# QuadCopterV2.net
KiCad netlist of a schematic drawn in EAGLE
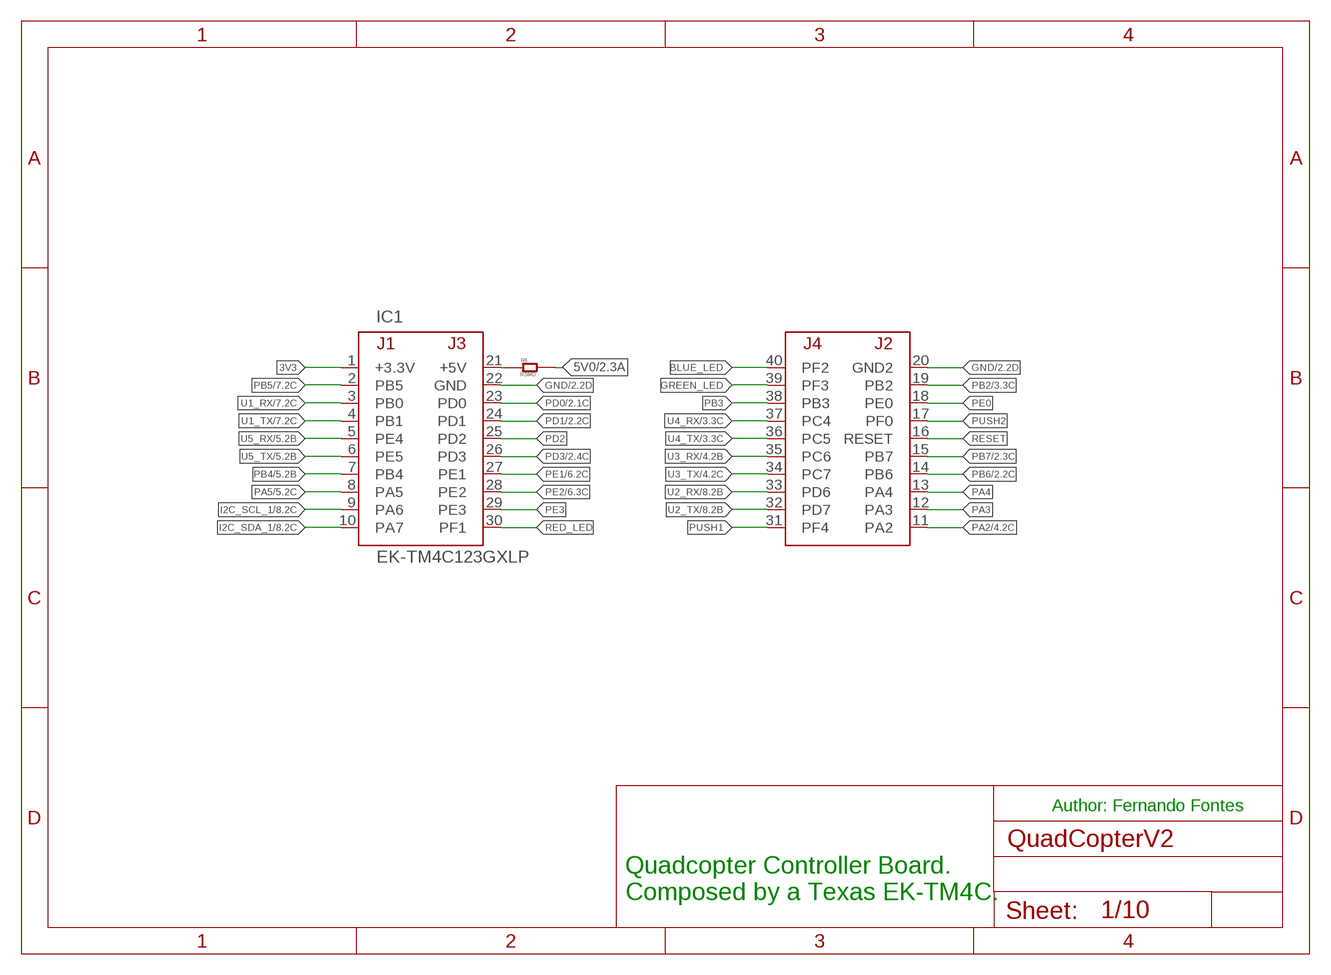
[diagram p0: schematic, sheet 1]
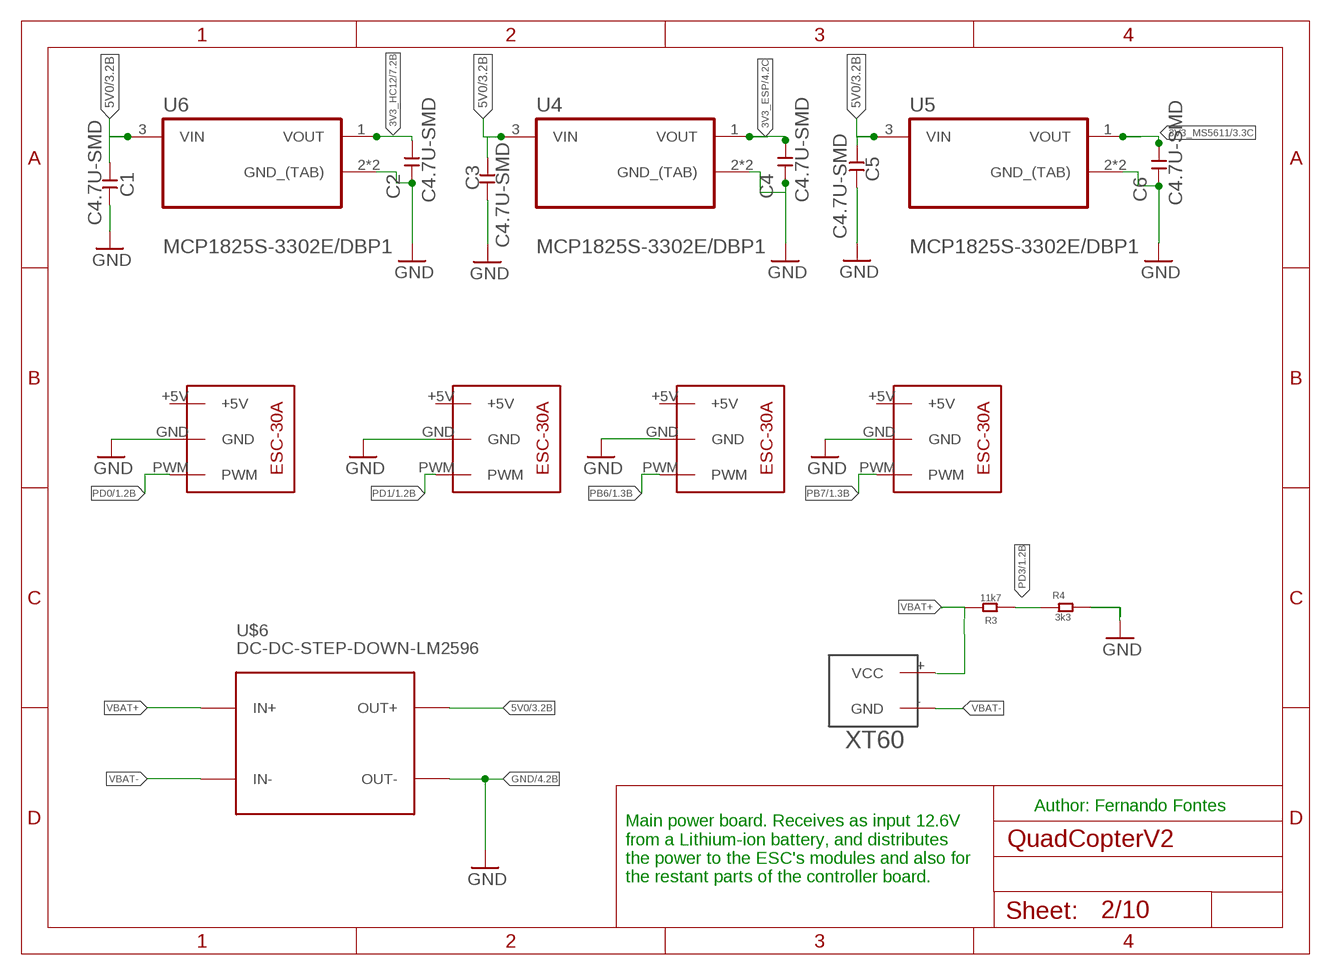
[diagram p1: schematic, sheet 2]
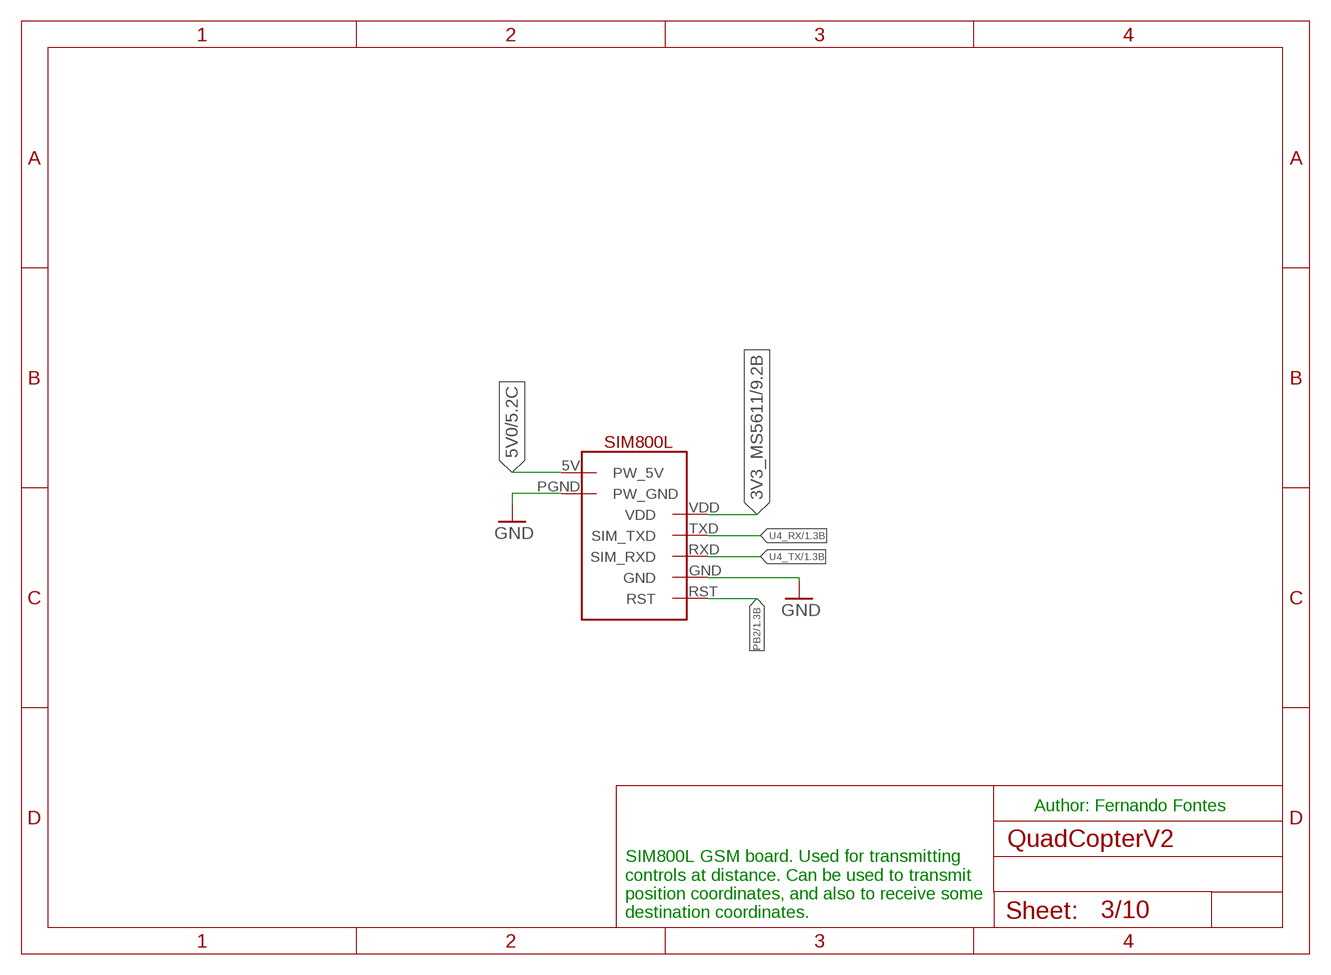
[diagram p2: schematic, sheet 3]
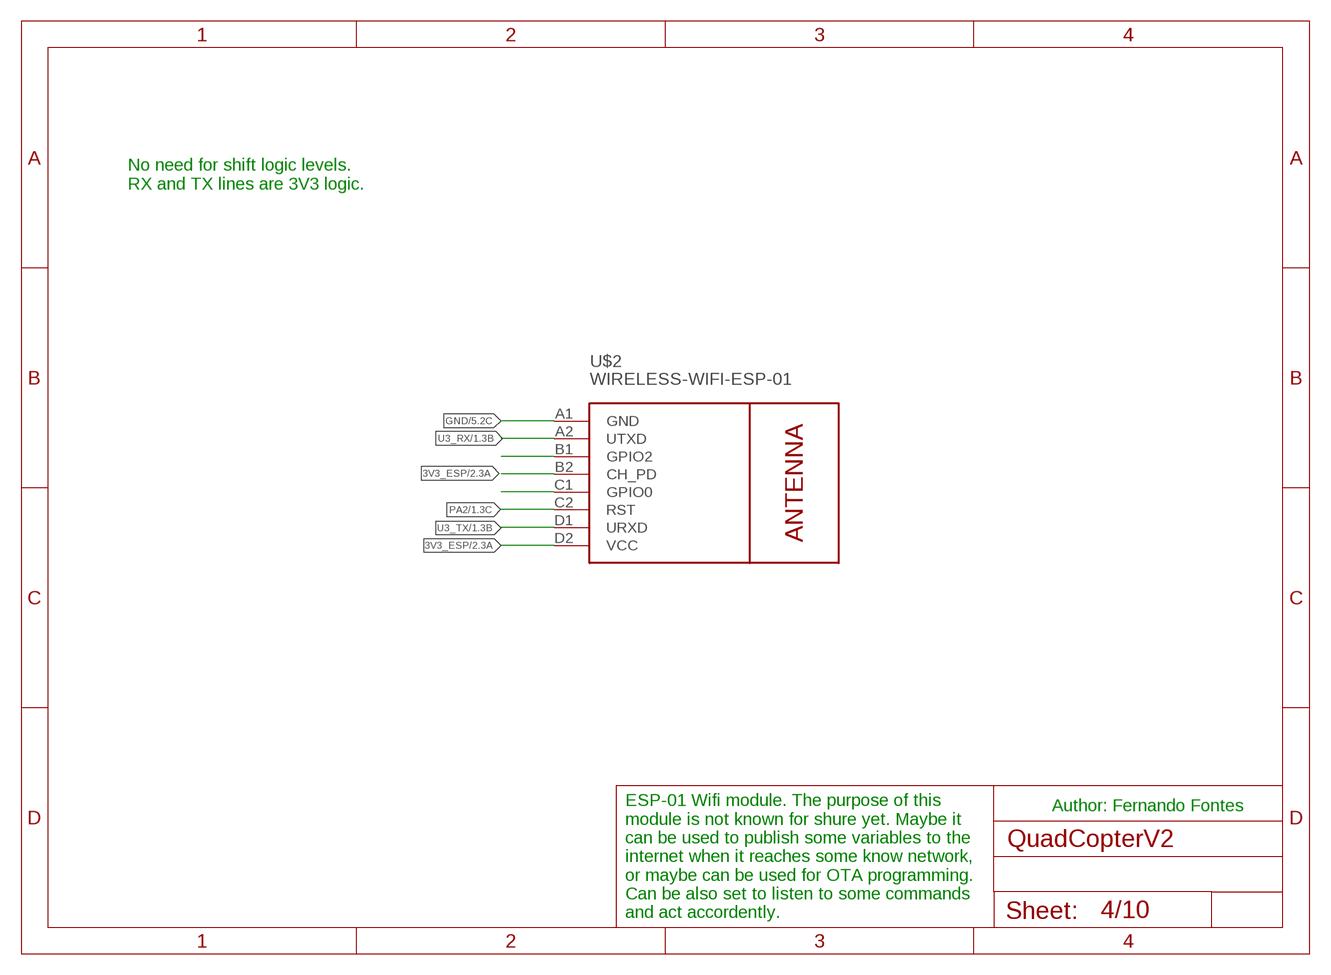
[diagram p3: schematic, sheet 4]
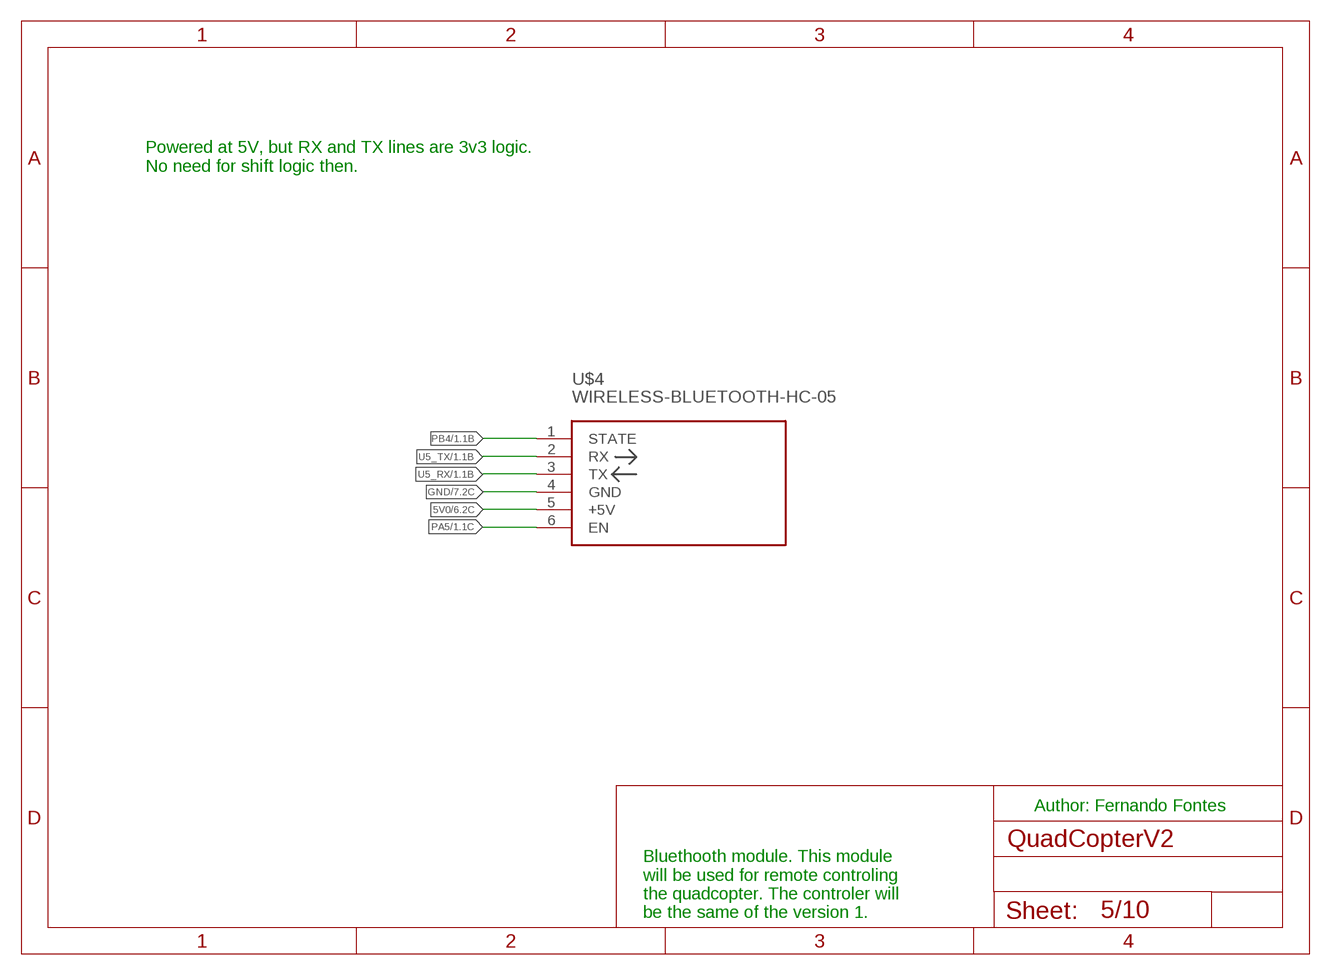
[diagram p4: schematic, sheet 5]
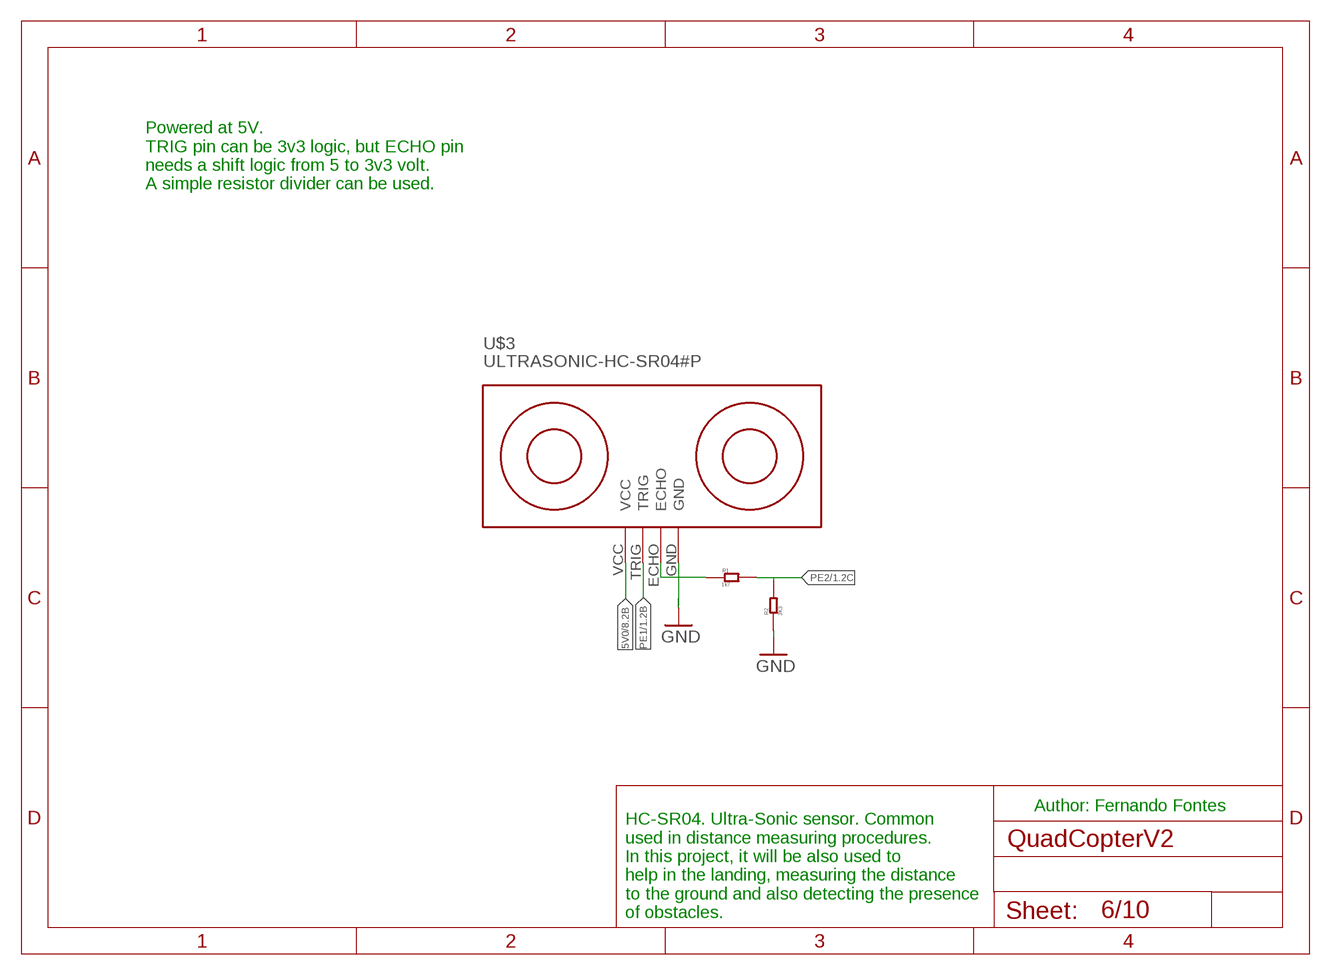
[diagram p5: schematic, sheet 6]
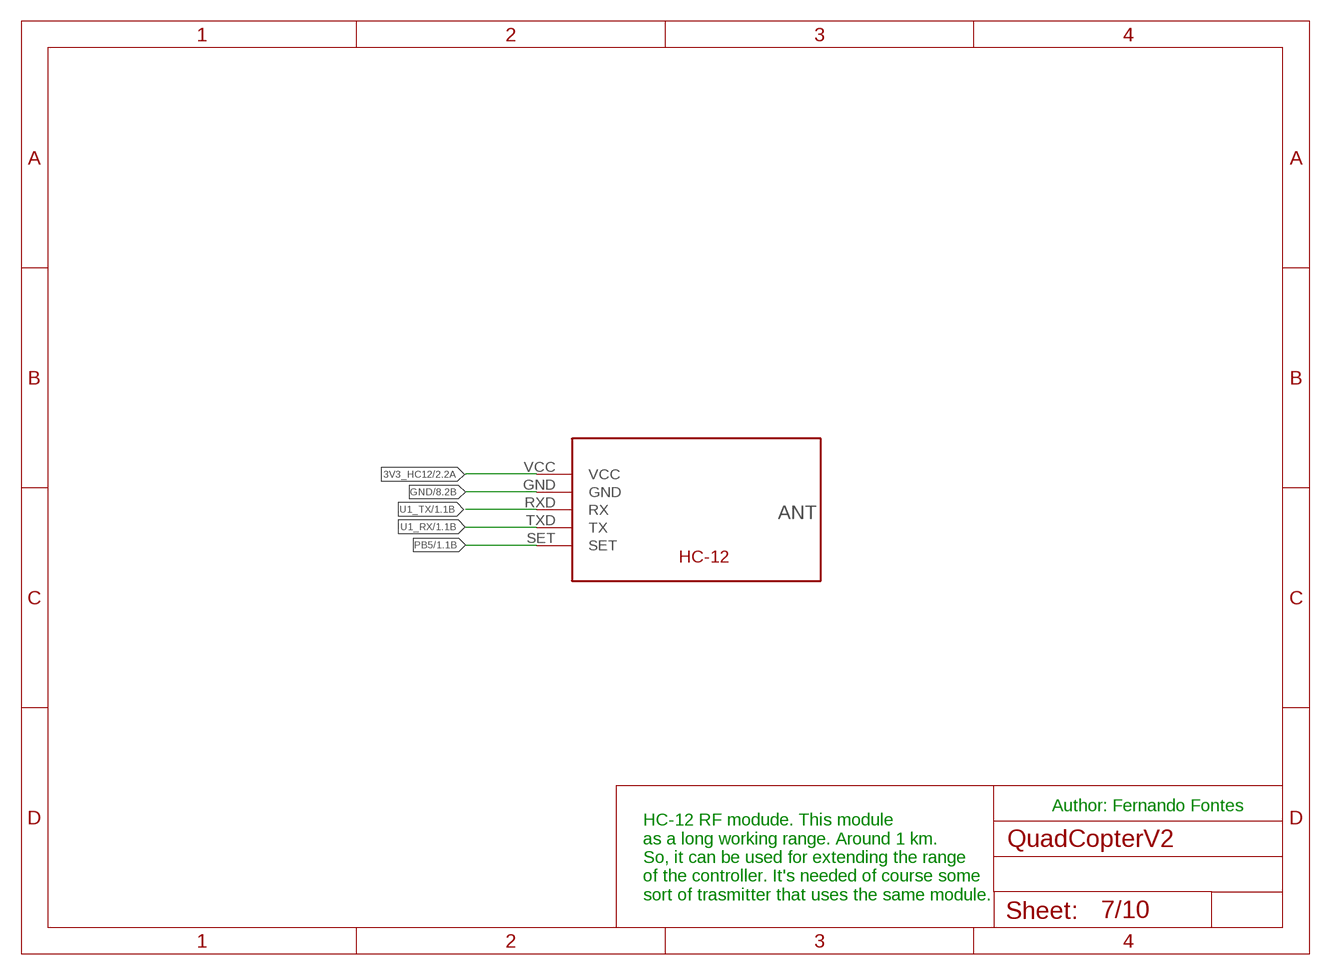
[diagram p6: schematic, sheet 7]
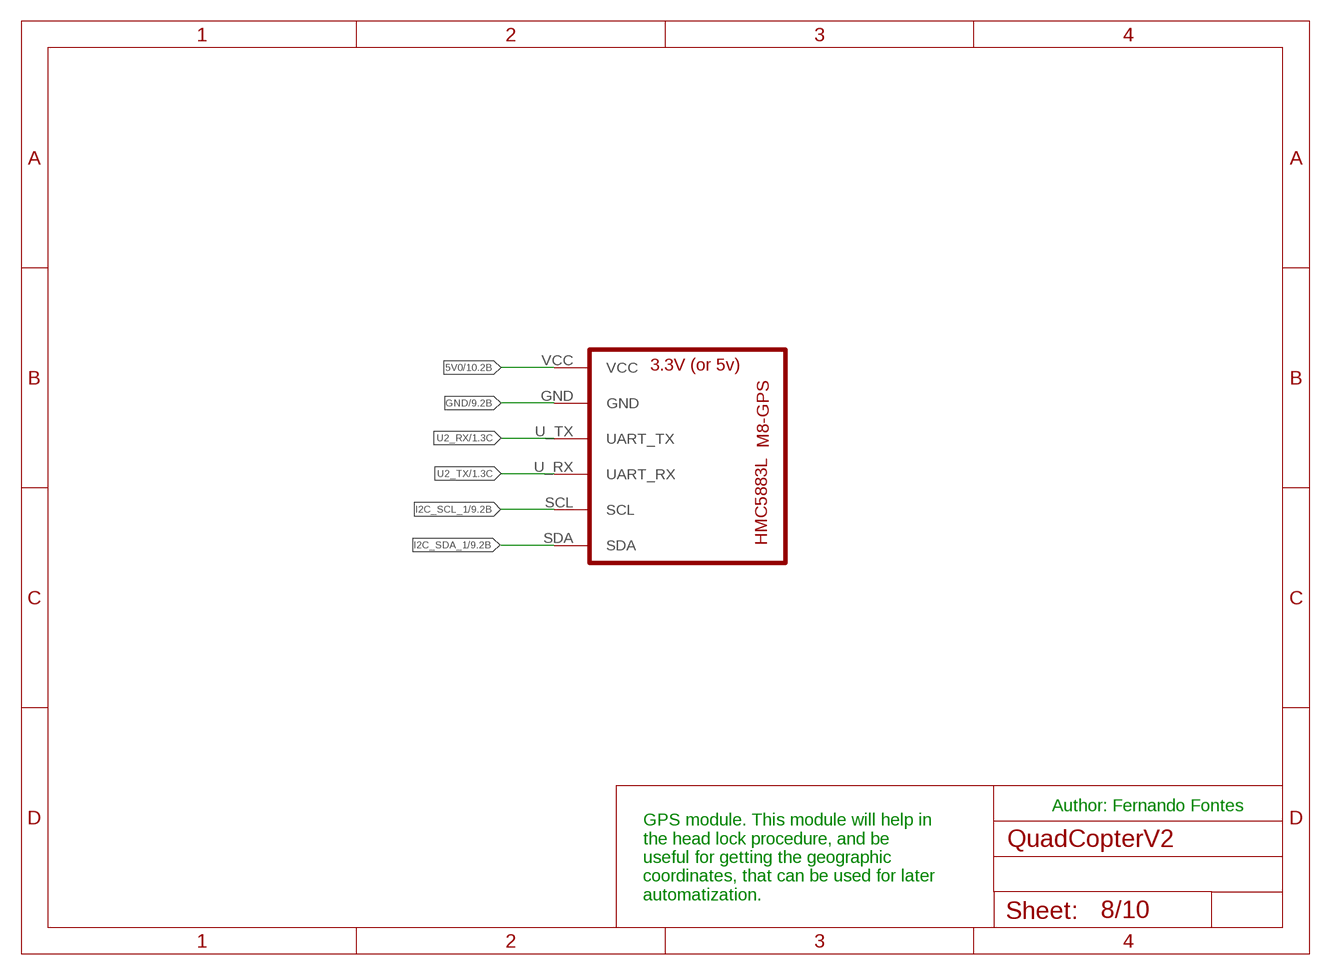
[diagram p7: schematic, sheet 8]
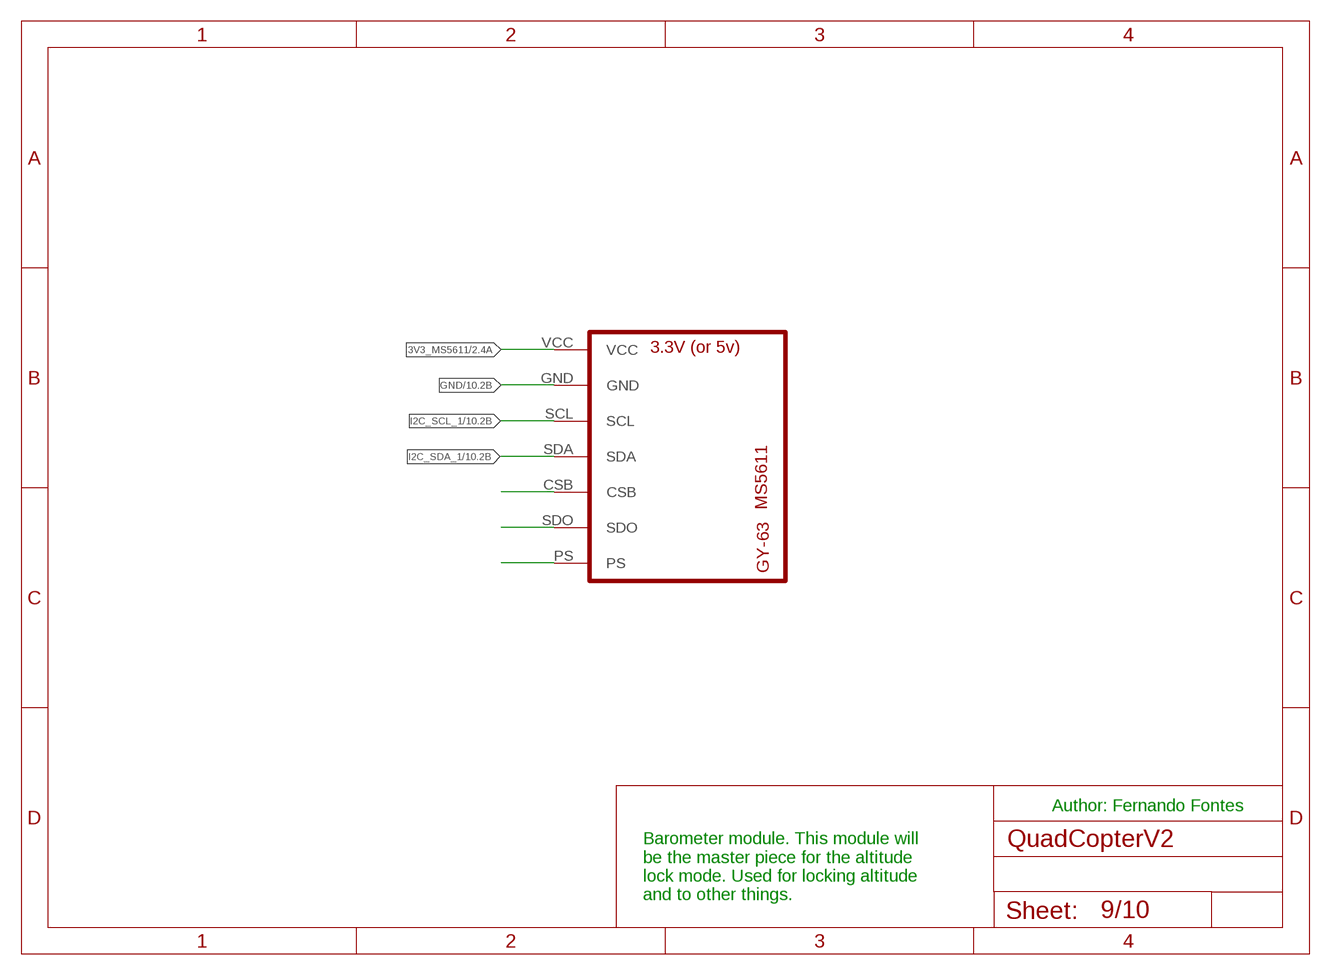
[diagram p8: schematic, sheet 9]
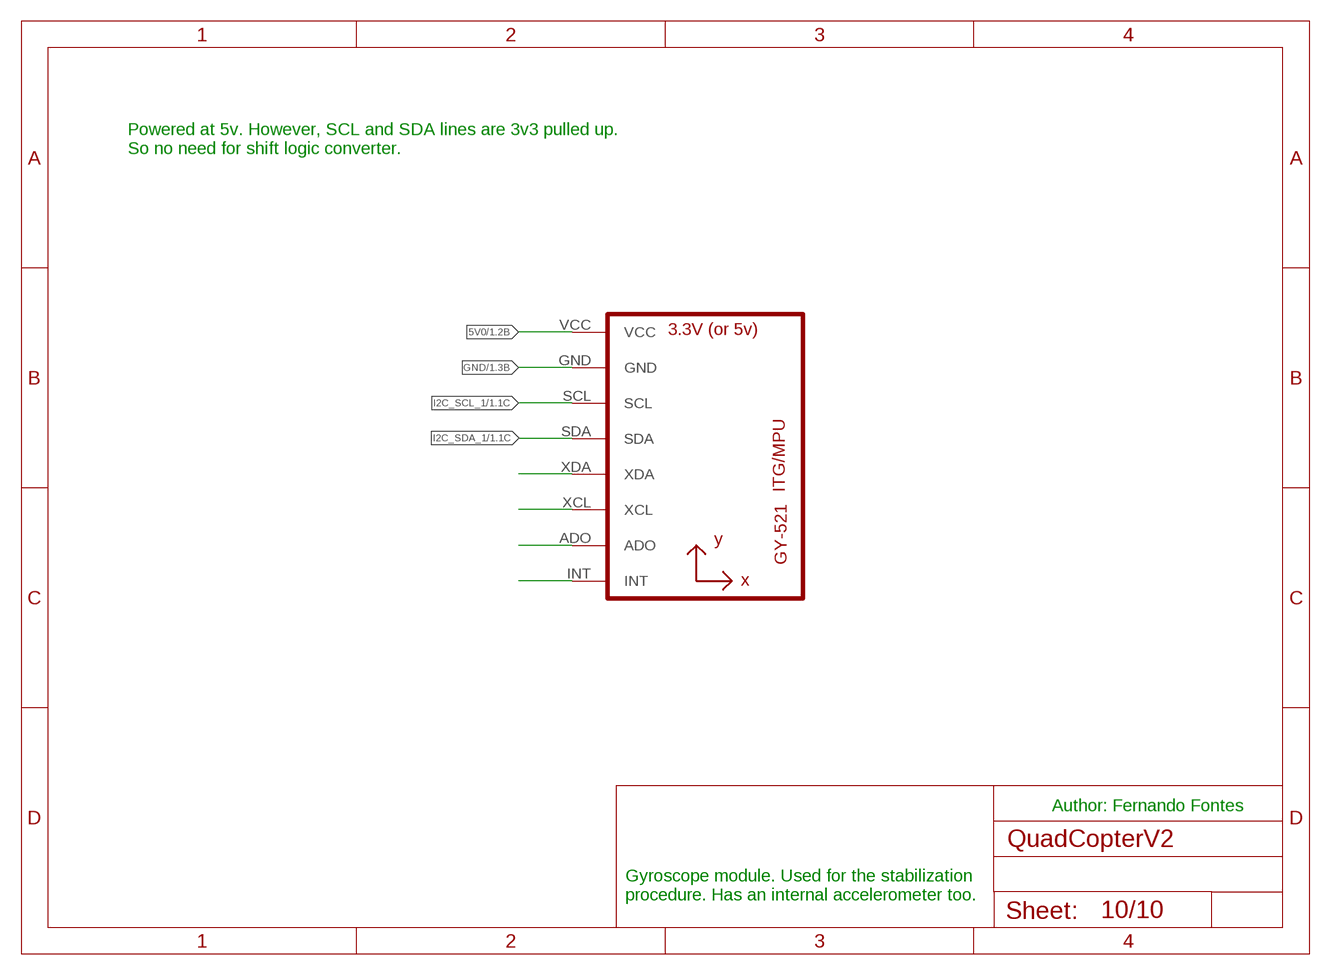
[diagram p9: schematic, sheet 10]

(export (version "E")
  (design (tool "Eeschema 10.0.6"))
  (components
    (comp (ref "U$5")
      (value "HC-12_FOOTPRINT")
      (footprint "eagle-import:HC-12_FOOTPRINT")
      (libsource (lib "eagle-import") (part "HC-12_FOOTPRINT"))
    )
    (comp (ref "U$1")
      (value "SIM800L")
      (footprint "eagle-import:SIP")
      (libsource (lib "eagle-import") (part "SIM800L"))
    )
    (comp (ref "U1")
      (value "GY-63MS5611")
      (footprint "eagle-import:GY-63")
      (libsource (lib "eagle-import") (part "GY-63MS5611"))
    )
    (comp (ref "U2")
      (value "GY-521MPU6050")
      (footprint "eagle-import:GY-521")
      (libsource (lib "eagle-import") (part "GY-521MPU6050"))
    )
    (comp (ref "IC1")
      (value "EK-TM4C123GXLP")
      (footprint "eagle-import:TM4C123LAUNCHPAD")
      (fields (field (name "MF") "Texas Instruments") (field (name "MP") "EK-TM4C123GXL"))
      (libsource (lib "eagle-import") (part "EK-TM4C123GXLP"))
    )
    (comp (ref "R6")
      (value "RSMD")
      (footprint "eagle-import:RSMD")
      (fields
        (field (name "COMMENT") "4-1614884-8")
        (field (name "MF") "TE Connectivity Passive Product")
        (field (name "MP") "CPF0805B220RE1")
      )
      (libsource (lib "eagle-import") (part "RSMD"))
    )
    (comp (ref "U3")
      (value "GY-63MS5611")
      (footprint "eagle-import:U-BLOX")
      (libsource (lib "eagle-import") (part "u_block_M8_GY-63MS5611"))
    )
    (comp (ref "R1")
      (value "1k7")
      (footprint "eagle-import:RSMD")
      (fields
        (field (name "COMMENT") "4-1614884-8")
        (field (name "MF") "TE Connectivity Passive Product")
        (field (name "MP") "CPF0805B220RE1")
      )
      (libsource (lib "eagle-import") (part "RSMD"))
    )
    (comp (ref "R2")
      (value "3K3")
      (footprint "eagle-import:RSMD")
      (fields
        (field (name "COMMENT") "4-1614884-8")
        (field (name "MF") "TE Connectivity Passive Product")
        (field (name "MP") "CPF0805B220RE1")
      )
      (libsource (lib "eagle-import") (part "RSMD"))
    )
    (comp (ref "U$3")
      (value "ULTRASONIC-HC-SR04#P")
      (footprint "eagle-import:ULTRASONIC-HC-SR04#P")
      (libsource (lib "eagle-import") (part "ULTRASONIC-HC-SR04#P"))
    )
    (comp (ref "C1")
      (value "C4.7U-SMD")
      (footprint "eagle-import:C4.7U-SMD")
      (libsource (lib "eagle-import") (part "C4.7U-SMD"))
    )
    (comp (ref "C2")
      (value "C4.7U-SMD")
      (footprint "eagle-import:C4.7U-SMD")
      (libsource (lib "eagle-import") (part "C4.7U-SMD"))
    )
    (comp (ref "C3")
      (value "C4.7U-SMD")
      (footprint "eagle-import:C4.7U-SMD")
      (libsource (lib "eagle-import") (part "C4.7U-SMD"))
    )
    (comp (ref "C4")
      (value "C4.7U-SMD")
      (footprint "eagle-import:C4.7U-SMD")
      (libsource (lib "eagle-import") (part "C4.7U-SMD"))
    )
    (comp (ref "C5")
      (value "C4.7U-SMD")
      (footprint "eagle-import:C4.7U-SMD")
      (libsource (lib "eagle-import") (part "C4.7U-SMD"))
    )
    (comp (ref "C6")
      (value "C4.7U-SMD")
      (footprint "eagle-import:C4.7U-SMD")
      (libsource (lib "eagle-import") (part "C4.7U-SMD"))
    )
    (comp (ref "R3")
      (value "11k7")
      (footprint "eagle-import:RSMD")
      (fields
        (field (name "COMMENT") "4-1614884-8")
        (field (name "MF") "TE Connectivity Passive Product")
        (field (name "MP") "CPF0805B220RE1")
      )
      (libsource (lib "eagle-import") (part "RSMD"))
    )
    (comp (ref "R4")
      (value "3k3")
      (footprint "eagle-import:RSMD")
      (fields
        (field (name "COMMENT") "4-1614884-8")
        (field (name "MF") "TE Connectivity Passive Product")
        (field (name "MP") "CPF0805B220RE1")
      )
      (libsource (lib "eagle-import") (part "RSMD"))
    )
    (comp (ref "U$6")
      (value "DC-DC-STEP-DOWN-LM2596")
      (footprint "eagle-import:DC-DC-STEP-DOWN-LM2596")
      (libsource (lib "eagle-import") (part "DC-DC-STEP-DOWN-LM2596"))
    )
    (comp (ref "U$7")
      (value "XT60")
      (footprint "eagle-import:XT60")
      (libsource (lib "eagle-import") (part "XT60"))
    )
    (comp (ref "U4")
      (value "MCP1825S-3302E/DBP1")
      (footprint "eagle-import:SOT230P700X180-4N#P1")
      (libsource (lib "eagle-import") (part "MCP1825S-3302E/DBP1"))
    )
    (comp (ref "U5")
      (value "MCP1825S-3302E/DBP1")
      (footprint "eagle-import:SOT230P700X180-4N#P1")
      (libsource (lib "eagle-import") (part "MCP1825S-3302E/DBP1"))
    )
    (comp (ref "U6")
      (value "MCP1825S-3302E/DBP1")
      (footprint "eagle-import:SOT230P700X180-4N#P1")
      (libsource (lib "eagle-import") (part "MCP1825S-3302E/DBP1"))
    )
    (comp (ref "U7")
      (value "ESC-30AMS5611")
      (footprint "eagle-import:ESC-30A")
      (libsource (lib "eagle-import") (part "ESC-30AMS5611"))
    )
    (comp (ref "U8")
      (value "ESC-30AMS5611")
      (footprint "eagle-import:ESC-30A")
      (libsource (lib "eagle-import") (part "ESC-30AMS5611"))
    )
    (comp (ref "U9")
      (value "ESC-30AMS5611")
      (footprint "eagle-import:ESC-30A")
      (libsource (lib "eagle-import") (part "ESC-30AMS5611"))
    )
    (comp (ref "U10")
      (value "ESC-30AMS5611")
      (footprint "eagle-import:ESC-30A")
      (libsource (lib "eagle-import") (part "ESC-30AMS5611"))
    )
    (comp (ref "U$2")
      (value "WIRELESS-WIFI-ESP-01")
      (footprint "eagle-import:WIRELESS-WIFI-ESP-01")
      (libsource (lib "eagle-import") (part "WIRELESS-WIFI-ESP-01"))
    )
    (comp (ref "U$4")
      (value "WIRELESS-BLUETOOTH-HC-05")
      (footprint "eagle-import:WIRELESS-BLUETOOTH-HC-05")
      (libsource (lib "eagle-import") (part "WIRELESS-BLUETOOTH-HC-05"))
    )
  )
  (nets
    (net (code "1") (name "3V3") (class "Default")
      (node (ref "IC1") (pin "1") (pinfunction "+3.3V_1") (pintype "power_in"))
    )
    (net (code "2") (name "3V3_ESP") (class "Default")
      (node (ref "C4") (pin "2") (pinfunction "2_2") (pintype "passive"))
      (node (ref "U$2") (pin "B2") (pinfunction "CH_PD_B2") (pintype "bidirectional"))
      (node (ref "U$2") (pin "D2") (pinfunction "VCC_D2") (pintype "power_in"))
      (node (ref "U4") (pin "1") (pinfunction "VOUT_1") (pintype "output"))
    )
    (net (code "3") (name "3V3_HC12") (class "Default")
      (node (ref "C2") (pin "2") (pinfunction "2_2") (pintype "passive"))
      (node (ref "U$5") (pin "VCC") (pinfunction "VCC_VCC") (pintype "bidirectional"))
      (node (ref "U6") (pin "1") (pinfunction "VOUT_1") (pintype "output"))
    )
    (net (code "4") (name "3V3_MS5611") (class "Default")
      (node (ref "C6") (pin "2") (pinfunction "2_2") (pintype "passive"))
      (node (ref "U$1") (pin "VDD") (pinfunction "VDD_VDD") (pintype "bidirectional"))
      (node (ref "U1") (pin "VCC") (pinfunction "VCC_VCC") (pintype "bidirectional"))
      (node (ref "U5") (pin "1") (pinfunction "VOUT_1") (pintype "output"))
    )
    (net (code "5") (name "5V0") (class "Default")
      (node (ref "C1") (pin "1") (pinfunction "1_1") (pintype "passive"))
      (node (ref "C3") (pin "2") (pinfunction "2_2") (pintype "passive"))
      (node (ref "C5") (pin "1") (pinfunction "1_1") (pintype "passive"))
      (node (ref "R6") (pin "2") (pinfunction "2_2") (pintype "passive"))
      (node (ref "U$1") (pin "5V") (pinfunction "PW_5V_5V") (pintype "bidirectional"))
      (node (ref "U$3") (pin "VCC") (pinfunction "VCC_VCC") (pintype "power_in"))
      (node (ref "U$4") (pin "5") (pinfunction "+5V_5") (pintype "power_in"))
      (node (ref "U$6") (pin "OUT+") (pinfunction "OUT+_OUT+") (pintype "bidirectional"))
      (node (ref "U2") (pin "VCC") (pinfunction "VCC_VCC") (pintype "bidirectional"))
      (node (ref "U3") (pin "VCC") (pinfunction "VCC_VCC") (pintype "bidirectional"))
      (node (ref "U4") (pin "3") (pinfunction "VIN_3") (pintype "input"))
      (node (ref "U5") (pin "3") (pinfunction "VIN_3") (pintype "input"))
      (node (ref "U6") (pin "3") (pinfunction "VIN_3") (pintype "input"))
    )
    (net (code "6") (name "BLUE_LED") (class "Default")
      (node (ref "IC1") (pin "40") (pinfunction "PF2_40") (pintype "bidirectional"))
    )
    (net (code "7") (name "GND") (class "Default")
      (node (ref "C1") (pin "2") (pinfunction "2_2") (pintype "passive"))
      (node (ref "C2") (pin "1") (pinfunction "1_1") (pintype "passive"))
      (node (ref "C3") (pin "1") (pinfunction "1_1") (pintype "passive"))
      (node (ref "C4") (pin "1") (pinfunction "1_1") (pintype "passive"))
      (node (ref "C5") (pin "2") (pinfunction "2_2") (pintype "passive"))
      (node (ref "C6") (pin "1") (pinfunction "1_1") (pintype "passive"))
      (node (ref "IC1") (pin "20") (pinfunction "GND2_20") (pintype "power_in"))
      (node (ref "IC1") (pin "22") (pinfunction "GND_22") (pintype "power_in"))
      (node (ref "R2") (pin "1") (pinfunction "1_1") (pintype "passive"))
      (node (ref "R4") (pin "2") (pinfunction "2_2") (pintype "passive"))
      (node (ref "U$1") (pin "GND") (pinfunction "GND_GND") (pintype "bidirectional"))
      (node (ref "U$1") (pin "PGND") (pinfunction "PW_GND_PGND") (pintype "bidirectional"))
      (node (ref "U$2") (pin "A1") (pinfunction "GND_A1") (pintype "power_in"))
      (node (ref "U$3") (pin "GND") (pinfunction "GND_GND") (pintype "power_in"))
      (node (ref "U$4") (pin "4") (pinfunction "GND_4") (pintype "power_in"))
      (node (ref "U$5") (pin "GND") (pinfunction "GND_GND") (pintype "bidirectional"))
      (node (ref "U$6") (pin "OUT-") (pinfunction "OUT-_OUT-") (pintype "bidirectional"))
      (node (ref "U1") (pin "GND") (pinfunction "GND_GND") (pintype "bidirectional"))
      (node (ref "U10") (pin "GND") (pinfunction "GND_GND") (pintype "bidirectional"))
      (node (ref "U2") (pin "GND") (pinfunction "GND_GND") (pintype "bidirectional"))
      (node (ref "U3") (pin "GND") (pinfunction "GND_GND") (pintype "bidirectional"))
      (node (ref "U4") (pin "2") (pinfunction "GND_(TAB)_2") (pintype "power_in"))
      (node (ref "U4") (pin "4") (pinfunction "GND_(TAB)_4") (pintype "power_in"))
      (node (ref "U5") (pin "2") (pinfunction "GND_(TAB)_2") (pintype "power_in"))
      (node (ref "U5") (pin "4") (pinfunction "GND_(TAB)_4") (pintype "power_in"))
      (node (ref "U6") (pin "2") (pinfunction "GND_(TAB)_2") (pintype "power_in"))
      (node (ref "U6") (pin "4") (pinfunction "GND_(TAB)_4") (pintype "power_in"))
      (node (ref "U7") (pin "GND") (pinfunction "GND_GND") (pintype "bidirectional"))
      (node (ref "U8") (pin "GND") (pinfunction "GND_GND") (pintype "bidirectional"))
      (node (ref "U9") (pin "GND") (pinfunction "GND_GND") (pintype "bidirectional"))
    )
    (net (code "8") (name "GREEN_LED") (class "Default")
      (node (ref "IC1") (pin "39") (pinfunction "PF3_39") (pintype "bidirectional"))
    )
    (net (code "9") (name "I2C_SCL_1") (class "Default")
      (node (ref "IC1") (pin "9") (pinfunction "PA6_9") (pintype "bidirectional"))
      (node (ref "U1") (pin "SCL") (pinfunction "SCL_SCL") (pintype "bidirectional"))
      (node (ref "U2") (pin "SCL") (pinfunction "SCL_SCL") (pintype "bidirectional"))
      (node (ref "U3") (pin "SCL") (pinfunction "SCL_SCL") (pintype "bidirectional"))
    )
    (net (code "10") (name "I2C_SDA_1") (class "Default")
      (node (ref "IC1") (pin "10") (pinfunction "PA7_10") (pintype "bidirectional"))
      (node (ref "U1") (pin "SDA") (pinfunction "SDA_SDA") (pintype "bidirectional"))
      (node (ref "U2") (pin "SDA") (pinfunction "SDA_SDA") (pintype "bidirectional"))
      (node (ref "U3") (pin "SDA") (pinfunction "SDA_SDA") (pintype "bidirectional"))
    )
    (net (code "11") (name "Net-(IC1-+5V)") (class "Default")
      (node (ref "IC1") (pin "21") (pinfunction "+5V_21") (pintype "power_in"))
      (node (ref "R6") (pin "1") (pinfunction "1_1") (pintype "passive"))
    )
    (net (code "12") (name "Net-(R1-Pad1)") (class "Default")
      (node (ref "R1") (pin "1") (pinfunction "1_1") (pintype "passive"))
      (node (ref "U$3") (pin "ECHO") (pinfunction "ECHO_ECHO") (pintype "output"))
    )
    (net (code "13") (name "PA2") (class "Default")
      (node (ref "IC1") (pin "11") (pinfunction "PA2_11") (pintype "bidirectional"))
      (node (ref "U$2") (pin "C2") (pinfunction "RST_C2") (pintype "bidirectional"))
    )
    (net (code "14") (name "PA3") (class "Default")
      (node (ref "IC1") (pin "12") (pinfunction "PA3_12") (pintype "bidirectional"))
    )
    (net (code "15") (name "PA4") (class "Default")
      (node (ref "IC1") (pin "13") (pinfunction "PA4_13") (pintype "bidirectional"))
    )
    (net (code "16") (name "PA5") (class "Default")
      (node (ref "IC1") (pin "8") (pinfunction "PA5_8") (pintype "bidirectional"))
      (node (ref "U$4") (pin "6") (pinfunction "EN_6") (pintype "bidirectional"))
    )
    (net (code "17") (name "PB2") (class "Default")
      (node (ref "IC1") (pin "19") (pinfunction "PB2_19") (pintype "bidirectional"))
      (node (ref "U$1") (pin "RST") (pinfunction "RST_RST") (pintype "bidirectional"))
    )
    (net (code "18") (name "PB3") (class "Default")
      (node (ref "IC1") (pin "38") (pinfunction "PB3_38") (pintype "bidirectional"))
    )
    (net (code "19") (name "PB4") (class "Default")
      (node (ref "IC1") (pin "7") (pinfunction "PB4_7") (pintype "bidirectional"))
      (node (ref "U$4") (pin "1") (pinfunction "STATE_1") (pintype "bidirectional"))
    )
    (net (code "20") (name "PB5") (class "Default")
      (node (ref "IC1") (pin "2") (pinfunction "PB5_2") (pintype "bidirectional"))
      (node (ref "U$5") (pin "SET") (pinfunction "SET_SET") (pintype "bidirectional"))
    )
    (net (code "21") (name "PB6") (class "Default")
      (node (ref "IC1") (pin "14") (pinfunction "PB6_14") (pintype "bidirectional"))
      (node (ref "U9") (pin "PWM") (pinfunction "PWM_PWM") (pintype "bidirectional"))
    )
    (net (code "22") (name "PB7") (class "Default")
      (node (ref "IC1") (pin "15") (pinfunction "PB7_15") (pintype "bidirectional"))
      (node (ref "U10") (pin "PWM") (pinfunction "PWM_PWM") (pintype "bidirectional"))
    )
    (net (code "23") (name "PD0") (class "Default")
      (node (ref "IC1") (pin "23") (pinfunction "PD0_23") (pintype "bidirectional"))
      (node (ref "U7") (pin "PWM") (pinfunction "PWM_PWM") (pintype "bidirectional"))
    )
    (net (code "24") (name "PD1") (class "Default")
      (node (ref "IC1") (pin "24") (pinfunction "PD1_24") (pintype "bidirectional"))
      (node (ref "U8") (pin "PWM") (pinfunction "PWM_PWM") (pintype "bidirectional"))
    )
    (net (code "25") (name "PD2") (class "Default")
      (node (ref "IC1") (pin "25") (pinfunction "PD2_25") (pintype "bidirectional"))
    )
    (net (code "26") (name "PD3") (class "Default")
      (node (ref "IC1") (pin "26") (pinfunction "PD3_26") (pintype "bidirectional"))
      (node (ref "R3") (pin "1") (pinfunction "1_1") (pintype "passive"))
      (node (ref "R4") (pin "1") (pinfunction "1_1") (pintype "passive"))
    )
    (net (code "27") (name "PE0") (class "Default")
      (node (ref "IC1") (pin "18") (pinfunction "PE0_18") (pintype "bidirectional"))
    )
    (net (code "28") (name "PE1") (class "Default")
      (node (ref "IC1") (pin "27") (pinfunction "PE1_27") (pintype "bidirectional"))
      (node (ref "U$3") (pin "TRIG") (pinfunction "TRIG_TRIG") (pintype "input"))
    )
    (net (code "29") (name "PE2") (class "Default")
      (node (ref "IC1") (pin "28") (pinfunction "PE2_28") (pintype "bidirectional"))
      (node (ref "R1") (pin "2") (pinfunction "2_2") (pintype "passive"))
      (node (ref "R2") (pin "2") (pinfunction "2_2") (pintype "passive"))
    )
    (net (code "30") (name "PE3") (class "Default")
      (node (ref "IC1") (pin "29") (pinfunction "PE3_29") (pintype "bidirectional"))
    )
    (net (code "31") (name "PUSH1") (class "Default")
      (node (ref "IC1") (pin "31") (pinfunction "PF4_31") (pintype "bidirectional"))
    )
    (net (code "32") (name "PUSH2") (class "Default")
      (node (ref "IC1") (pin "17") (pinfunction "PF0_17") (pintype "bidirectional"))
    )
    (net (code "33") (name "RED_LED") (class "Default")
      (node (ref "IC1") (pin "30") (pinfunction "PF1_30") (pintype "bidirectional"))
    )
    (net (code "34") (name "RESET") (class "Default")
      (node (ref "IC1") (pin "16") (pinfunction "RESET_16") (pintype "input"))
    )
    (net (code "35") (name "U1_RX") (class "Default")
      (node (ref "IC1") (pin "3") (pinfunction "PB0_3") (pintype "bidirectional"))
      (node (ref "U$5") (pin "TXD") (pinfunction "TX_TXD") (pintype "bidirectional"))
    )
    (net (code "36") (name "U1_TX") (class "Default")
      (node (ref "IC1") (pin "4") (pinfunction "PB1_4") (pintype "bidirectional"))
      (node (ref "U$5") (pin "RXD") (pinfunction "RX_RXD") (pintype "bidirectional"))
    )
    (net (code "37") (name "U2_RX") (class "Default")
      (node (ref "IC1") (pin "33") (pinfunction "PD6_33") (pintype "bidirectional"))
      (node (ref "U3") (pin "U_TX") (pinfunction "UART_TX_U_TX") (pintype "bidirectional"))
    )
    (net (code "38") (name "U2_TX") (class "Default")
      (node (ref "IC1") (pin "32") (pinfunction "PD7_32") (pintype "bidirectional"))
      (node (ref "U3") (pin "U_RX") (pinfunction "UART_RX_U_RX") (pintype "bidirectional"))
    )
    (net (code "39") (name "U3_RX") (class "Default")
      (node (ref "IC1") (pin "35") (pinfunction "PC6_35") (pintype "bidirectional"))
      (node (ref "U$2") (pin "A2") (pinfunction "UTXD_A2") (pintype "bidirectional"))
    )
    (net (code "40") (name "U3_TX") (class "Default")
      (node (ref "IC1") (pin "34") (pinfunction "PC7_34") (pintype "bidirectional"))
      (node (ref "U$2") (pin "D1") (pinfunction "URXD_D1") (pintype "bidirectional"))
    )
    (net (code "41") (name "U4_RX") (class "Default")
      (node (ref "IC1") (pin "37") (pinfunction "PC4_37") (pintype "bidirectional"))
      (node (ref "U$1") (pin "TXD") (pinfunction "SIM_TXD_TXD") (pintype "bidirectional"))
    )
    (net (code "42") (name "U4_TX") (class "Default")
      (node (ref "IC1") (pin "36") (pinfunction "PC5_36") (pintype "bidirectional"))
      (node (ref "U$1") (pin "RXD") (pinfunction "SIM_RXD_RXD") (pintype "bidirectional"))
    )
    (net (code "43") (name "U5_RX") (class "Default")
      (node (ref "IC1") (pin "5") (pinfunction "PE4_5") (pintype "bidirectional"))
      (node (ref "U$4") (pin "3") (pinfunction "TX_3") (pintype "bidirectional"))
    )
    (net (code "44") (name "U5_TX") (class "Default")
      (node (ref "IC1") (pin "6") (pinfunction "PE5_6") (pintype "bidirectional"))
      (node (ref "U$4") (pin "2") (pinfunction "RX_2") (pintype "bidirectional"))
    )
    (net (code "45") (name "VBAT+") (class "Default")
      (node (ref "R3") (pin "2") (pinfunction "2_2") (pintype "passive"))
      (node (ref "U$6") (pin "IN+") (pinfunction "IN+_IN+") (pintype "bidirectional"))
      (node (ref "U$7") (pin "+") (pinfunction "VCC_+") (pintype "bidirectional"))
    )
    (net (code "46") (name "VBAT-") (class "Default")
      (node (ref "U$6") (pin "IN-") (pinfunction "IN-_IN-") (pintype "bidirectional"))
      (node (ref "U$7") (pin "-") (pinfunction "GND_-") (pintype "bidirectional"))
    )
    (net (code "47") (name "unconnected-(U$2-GPIO0-PadC1)") (class "Default")
      (node (ref "U$2") (pin "C1") (pinfunction "GPIO0_C1") (pintype "bidirectional"))
    )
    (net (code "48") (name "unconnected-(U$2-GPIO2-PadB1)") (class "Default")
      (node (ref "U$2") (pin "B1") (pinfunction "GPIO2_B1") (pintype "bidirectional"))
    )
    (net (code "49") (name "unconnected-(U1-PadCSB)") (class "Default")
      (node (ref "U1") (pin "CSB") (pinfunction "CSB_CSB") (pintype "bidirectional"))
    )
    (net (code "50") (name "unconnected-(U1-PadPS)") (class "Default")
      (node (ref "U1") (pin "PS") (pinfunction "PS_PS") (pintype "bidirectional"))
    )
    (net (code "51") (name "unconnected-(U1-PadSDO)") (class "Default")
      (node (ref "U1") (pin "SDO") (pinfunction "SDO_SDO") (pintype "bidirectional"))
    )
    (net (code "52") (name "unconnected-(U2-PadADO)") (class "Default")
      (node (ref "U2") (pin "ADO") (pinfunction "ADO_ADO") (pintype "bidirectional"))
    )
    (net (code "53") (name "unconnected-(U2-PadINT)") (class "Default")
      (node (ref "U2") (pin "INT") (pinfunction "INT_INT") (pintype "bidirectional"))
    )
    (net (code "54") (name "unconnected-(U2-PadXCL)") (class "Default")
      (node (ref "U2") (pin "XCL") (pinfunction "XCL_XCL") (pintype "bidirectional"))
    )
    (net (code "55") (name "unconnected-(U2-PadXDA)") (class "Default")
      (node (ref "U2") (pin "XDA") (pinfunction "XDA_XDA") (pintype "bidirectional"))
    )
    (net (code "56") (name "unconnected-(U7-Pad+5V)") (class "Default")
      (node (ref "U7") (pin "+5V") (pinfunction "+5V_+5V") (pintype "bidirectional"))
    )
    (net (code "57") (name "unconnected-(U8-Pad+5V)") (class "Default")
      (node (ref "U8") (pin "+5V") (pinfunction "+5V_+5V") (pintype "bidirectional"))
    )
    (net (code "58") (name "unconnected-(U9-Pad+5V)") (class "Default")
      (node (ref "U9") (pin "+5V") (pinfunction "+5V_+5V") (pintype "bidirectional"))
    )
    (net (code "59") (name "unconnected-(U10-Pad+5V)") (class "Default")
      (node (ref "U10") (pin "+5V") (pinfunction "+5V_+5V") (pintype "bidirectional"))
    )
  )
)
